# Motherboard.net
KiCad netlist of a schematic drawn in EAGLE
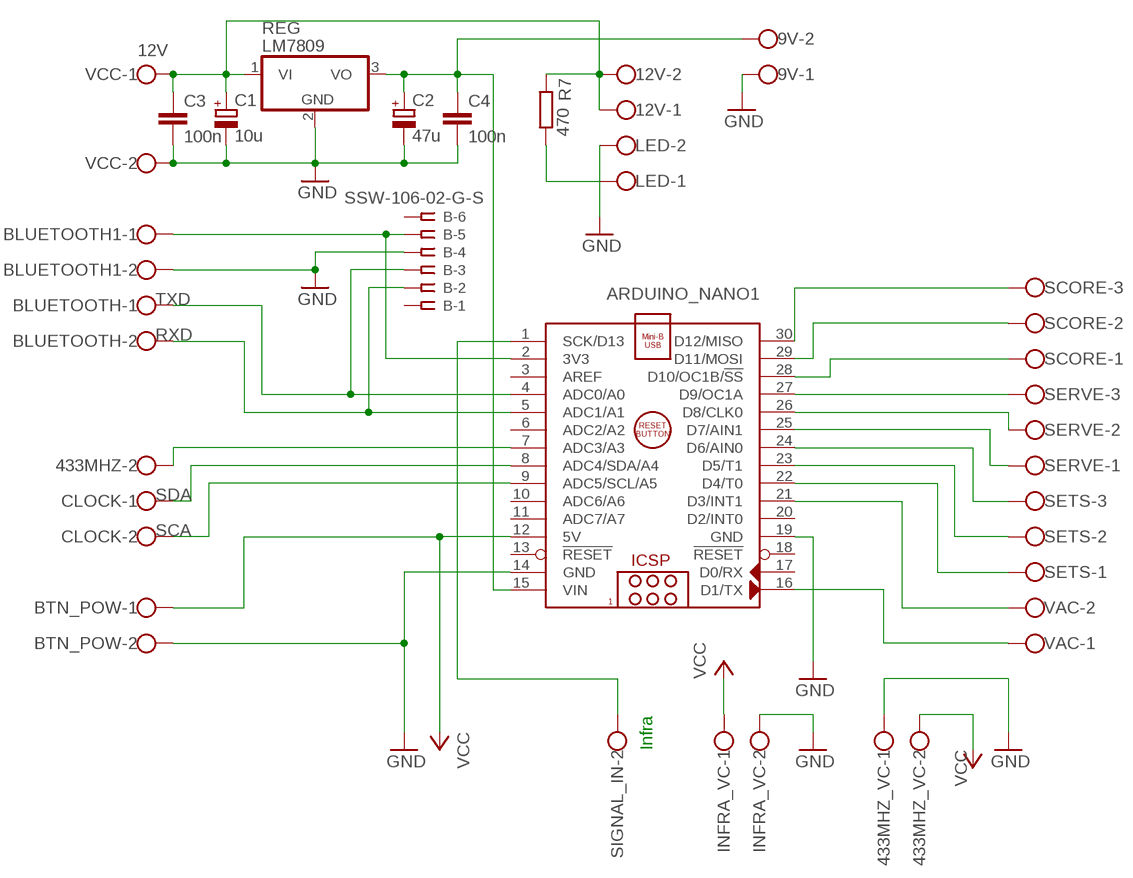
[diagram p0: schematic, sheet 1]

(export (version "E")
  (design (tool "Eeschema 10.0.6"))
  (components
    (comp (ref "9V")
      (value "W237-102")
      (footprint "eagle-import:W237-102")
      (fields (field (name "MPN") "237-102"))
      (libsource (lib "eagle-import") (part "W237-102"))
    )
    (comp (ref "12V")
      (value "W237-102")
      (footprint "eagle-import:W237-102")
      (fields (field (name "MPN") "237-102"))
      (libsource (lib "eagle-import") (part "W237-102"))
    )
    (comp (ref "433MHZ")
      (value "W237-102")
      (footprint "eagle-import:W237-102")
      (fields (field (name "MPN") "237-102"))
      (libsource (lib "eagle-import") (part "W237-102"))
    )
    (comp (ref "433MHZ_VC")
      (value "W237-102")
      (footprint "eagle-import:W237-102")
      (fields (field (name "MPN") "237-102"))
      (libsource (lib "eagle-import") (part "W237-102"))
    )
    (comp (ref "ARDUINO_NANO1")
      (value "ARDUINO_NANO")
      (footprint "eagle-import:ARDUINO_NANO")
      (libsource (lib "eagle-import") (part "ARDUINO_NANO"))
    )
    (comp (ref "B")
      (value "SSW-106-02-G-S")
      (footprint "eagle-import:SSW-106-02-G-S")
      (fields (field (name "MF") "Samtec Inc."))
      (libsource (lib "eagle-import") (part "SSW-106-02-G-S"))
    )
    (comp (ref "BLUETOOTH")
      (value "W237-102")
      (footprint "eagle-import:W237-102")
      (fields (field (name "MPN") "237-102"))
      (libsource (lib "eagle-import") (part "W237-102"))
    )
    (comp (ref "BLUETOOTH1")
      (value "W237-102")
      (footprint "eagle-import:W237-102")
      (fields (field (name "MPN") "237-102"))
      (libsource (lib "eagle-import") (part "W237-102"))
    )
    (comp (ref "BTN_POW")
      (value "W237-102")
      (footprint "eagle-import:W237-102")
      (fields (field (name "MPN") "237-102"))
      (libsource (lib "eagle-import") (part "W237-102"))
    )
    (comp (ref "C1")
      (value "10u")
      (footprint "eagle-import:E2-4")
      (libsource (lib "eagle-import") (part "CPOL-EUE2-4"))
    )
    (comp (ref "C2")
      (value "47u")
      (footprint "eagle-import:E2-4")
      (libsource (lib "eagle-import") (part "CPOL-EUE2-4"))
    )
    (comp (ref "C3")
      (value "100n")
      (footprint "eagle-import:C5B2.5")
      (libsource (lib "eagle-import") (part "C5/2.5"))
    )
    (comp (ref "C4")
      (value "100n")
      (footprint "eagle-import:C5B2.5")
      (libsource (lib "eagle-import") (part "C5/2.5"))
    )
    (comp (ref "CLOCK")
      (value "W237-102")
      (footprint "eagle-import:W237-102")
      (fields (field (name "MPN") "237-102"))
      (libsource (lib "eagle-import") (part "W237-102"))
    )
    (comp (ref "INFRA_VC")
      (value "W237-102")
      (footprint "eagle-import:W237-102")
      (fields (field (name "MPN") "237-102"))
      (libsource (lib "eagle-import") (part "W237-102"))
    )
    (comp (ref "LED")
      (value "W237-102")
      (footprint "eagle-import:W237-102")
      (fields (field (name "MPN") "237-102"))
      (libsource (lib "eagle-import") (part "W237-102"))
    )
    (comp (ref "R7")
      (value "470")
      (footprint "eagle-import:0204_7")
      (libsource (lib "eagle-import") (part "R-EU_0204/7"))
    )
    (comp (ref "REG")
      (value "LM7809")
      (footprint "eagle-import:TO220H")
      (libsource (lib "eagle-import") (part "78T05"))
    )
    (comp (ref "SCORE")
      (value "W237-103")
      (footprint "eagle-import:W237-103")
      (fields (field (name "MPN") "237-103"))
      (libsource (lib "eagle-import") (part "W237-103"))
    )
    (comp (ref "SERVE")
      (value "W237-103")
      (footprint "eagle-import:W237-103")
      (fields (field (name "MPN") "237-103"))
      (libsource (lib "eagle-import") (part "W237-103"))
    )
    (comp (ref "SETS")
      (value "W237-103")
      (footprint "eagle-import:W237-103")
      (fields (field (name "MPN") "237-103"))
      (libsource (lib "eagle-import") (part "W237-103"))
    )
    (comp (ref "SIGNAL_IN")
      (value "W237-102")
      (footprint "eagle-import:W237-102")
      (fields (field (name "MPN") "237-102"))
      (libsource (lib "eagle-import") (part "W237-102"))
    )
    (comp (ref "VAC")
      (value "W237-102")
      (footprint "eagle-import:W237-102")
      (fields (field (name "MPN") "237-102"))
      (libsource (lib "eagle-import") (part "W237-102"))
    )
    (comp (ref "VCC")
      (value "W237-102")
      (footprint "eagle-import:W237-102")
      (fields (field (name "MPN") "237-102"))
      (libsource (lib "eagle-import") (part "W237-102"))
    )
  )
  (nets
    (net (code "1") (name "/12V") (class "Default")
      (node (ref "12V") (pin "1") (pinfunction "KL_1") (pintype "passive"))
      (node (ref "12V") (pin "2") (pinfunction "KL_2") (pintype "passive"))
      (node (ref "C1") (pin "+") (pinfunction "+_+") (pintype "passive"))
      (node (ref "C3") (pin "1") (pinfunction "1_1") (pintype "passive"))
      (node (ref "R7") (pin "2") (pinfunction "2_2") (pintype "passive"))
      (node (ref "REG") (pin "1") (pinfunction "VI_1") (pintype "input"))
      (node (ref "VCC") (pin "1") (pinfunction "KL_1") (pintype "passive"))
    )
    (net (code "2") (name "GND") (class "Default")
      (node (ref "433MHZ_VC") (pin "1") (pinfunction "KL_1") (pintype "passive"))
      (node (ref "9V") (pin "1") (pinfunction "KL_1") (pintype "passive"))
      (node (ref "ARDUINO_NANO1") (pin "14") (pinfunction "GND_14") (pintype "power_in"))
      (node (ref "ARDUINO_NANO1") (pin "19") (pinfunction "GND_19") (pintype "power_in"))
      (node (ref "B") (pin "4") (pinfunction "1_4") (pintype "passive"))
      (node (ref "BLUETOOTH1") (pin "2") (pinfunction "KL_2") (pintype "passive"))
      (node (ref "BTN_POW") (pin "2") (pinfunction "KL_2") (pintype "passive"))
      (node (ref "C1") (pin "-") (pinfunction "-_-") (pintype "passive"))
      (node (ref "C2") (pin "-") (pinfunction "-_-") (pintype "passive"))
      (node (ref "C3") (pin "2") (pinfunction "2_2") (pintype "passive"))
      (node (ref "C4") (pin "2") (pinfunction "2_2") (pintype "passive"))
      (node (ref "INFRA_VC") (pin "2") (pinfunction "KL_2") (pintype "passive"))
      (node (ref "LED") (pin "2") (pinfunction "KL_2") (pintype "passive"))
      (node (ref "REG") (pin "2") (pinfunction "GND_2") (pintype "passive"))
      (node (ref "VCC") (pin "2") (pinfunction "KL_2") (pintype "passive"))
    )
    (net (code "3") (name "Net-(9VB-KL)") (class "Default")
      (node (ref "9V") (pin "2") (pinfunction "KL_2") (pintype "passive"))
      (node (ref "ARDUINO_NANO1") (pin "15") (pinfunction "VIN_15") (pintype "power_in"))
      (node (ref "C2") (pin "+") (pinfunction "+_+") (pintype "passive"))
      (node (ref "C4") (pin "1") (pinfunction "1_1") (pintype "passive"))
      (node (ref "REG") (pin "3") (pinfunction "VO_3") (pintype "passive"))
    )
    (net (code "4") (name "Net-(433MHZB-KL)") (class "Default")
      (node (ref "433MHZ") (pin "2") (pinfunction "KL_2") (pintype "passive"))
      (node (ref "ARDUINO_NANO1") (pin "7") (pinfunction "ADC3/A3_7") (pintype "bidirectional"))
    )
    (net (code "5") (name "Net-(ARDUINO_NANO1-3V3)") (class "Default")
      (node (ref "ARDUINO_NANO1") (pin "2") (pinfunction "3V3_2") (pintype "output"))
      (node (ref "B") (pin "5") (pinfunction "1_5") (pintype "passive"))
      (node (ref "BLUETOOTH1") (pin "1") (pinfunction "KL_1") (pintype "passive"))
    )
    (net (code "6") (name "Net-(ARDUINO_NANO1-ADC0{slash}A0)") (class "Default")
      (node (ref "ARDUINO_NANO1") (pin "4") (pinfunction "ADC0/A0_4") (pintype "bidirectional"))
      (node (ref "B") (pin "3") (pinfunction "1_3") (pintype "passive"))
      (node (ref "BLUETOOTH") (pin "1") (pinfunction "KL_1") (pintype "passive"))
    )
    (net (code "7") (name "Net-(ARDUINO_NANO1-ADC1{slash}A1)") (class "Default")
      (node (ref "ARDUINO_NANO1") (pin "5") (pinfunction "ADC1/A1_5") (pintype "bidirectional"))
      (node (ref "B") (pin "2") (pinfunction "1_2") (pintype "passive"))
      (node (ref "BLUETOOTH") (pin "2") (pinfunction "KL_2") (pintype "passive"))
    )
    (net (code "8") (name "Net-(ARDUINO_NANO1-ADC4{slash}SDA{slash}A4)") (class "Default")
      (node (ref "ARDUINO_NANO1") (pin "8") (pinfunction "ADC4/SDA/A4_8") (pintype "bidirectional"))
      (node (ref "CLOCK") (pin "1") (pinfunction "KL_1") (pintype "passive"))
    )
    (net (code "9") (name "Net-(ARDUINO_NANO1-ADC5{slash}SCL{slash}A5)") (class "Default")
      (node (ref "ARDUINO_NANO1") (pin "9") (pinfunction "ADC5/SCL/A5_9") (pintype "bidirectional"))
      (node (ref "CLOCK") (pin "2") (pinfunction "KL_2") (pintype "passive"))
    )
    (net (code "10") (name "Net-(ARDUINO_NANO1-D1{slash}TX)") (class "Default")
      (node (ref "ARDUINO_NANO1") (pin "16") (pinfunction "D1/TX_16") (pintype "bidirectional"))
      (node (ref "VAC") (pin "1") (pinfunction "KL_1") (pintype "passive"))
    )
    (net (code "11") (name "Net-(ARDUINO_NANO1-D3{slash}INT1)") (class "Default")
      (node (ref "ARDUINO_NANO1") (pin "21") (pinfunction "D3/INT1_21") (pintype "bidirectional"))
      (node (ref "VAC") (pin "2") (pinfunction "KL_2") (pintype "passive"))
    )
    (net (code "12") (name "Net-(ARDUINO_NANO1-D4{slash}T0)") (class "Default")
      (node (ref "ARDUINO_NANO1") (pin "22") (pinfunction "D4/T0_22") (pintype "bidirectional"))
      (node (ref "SETS") (pin "1") (pinfunction "KL_1") (pintype "passive"))
    )
    (net (code "13") (name "Net-(ARDUINO_NANO1-D5{slash}T1)") (class "Default")
      (node (ref "ARDUINO_NANO1") (pin "23") (pinfunction "D5/T1_23") (pintype "bidirectional"))
      (node (ref "SETS") (pin "2") (pinfunction "KL_2") (pintype "passive"))
    )
    (net (code "14") (name "Net-(ARDUINO_NANO1-D6{slash}AIN0)") (class "Default")
      (node (ref "ARDUINO_NANO1") (pin "24") (pinfunction "D6/AIN0_24") (pintype "bidirectional"))
      (node (ref "SETS") (pin "3") (pinfunction "KL_3") (pintype "passive"))
    )
    (net (code "15") (name "Net-(ARDUINO_NANO1-D7{slash}AIN1)") (class "Default")
      (node (ref "ARDUINO_NANO1") (pin "25") (pinfunction "D7/AIN1_25") (pintype "bidirectional"))
      (node (ref "SERVE") (pin "1") (pinfunction "KL_1") (pintype "passive"))
    )
    (net (code "16") (name "Net-(ARDUINO_NANO1-D8{slash}CLK0)") (class "Default")
      (node (ref "ARDUINO_NANO1") (pin "26") (pinfunction "D8/CLK0_26") (pintype "bidirectional"))
      (node (ref "SERVE") (pin "2") (pinfunction "KL_2") (pintype "passive"))
    )
    (net (code "17") (name "Net-(ARDUINO_NANO1-D9{slash}OC1A)") (class "Default")
      (node (ref "ARDUINO_NANO1") (pin "27") (pinfunction "D9/OC1A_27") (pintype "bidirectional"))
      (node (ref "SERVE") (pin "3") (pinfunction "KL_3") (pintype "passive"))
    )
    (net (code "18") (name "Net-(ARDUINO_NANO1-D10{slash}OC1B{slash}~{SS})") (class "Default")
      (node (ref "ARDUINO_NANO1") (pin "28") (pinfunction "D10/OC1B/~{SS}_28") (pintype "bidirectional"))
      (node (ref "SCORE") (pin "1") (pinfunction "KL_1") (pintype "passive"))
    )
    (net (code "19") (name "Net-(ARDUINO_NANO1-D11{slash}MOSI)") (class "Default")
      (node (ref "ARDUINO_NANO1") (pin "29") (pinfunction "D11/MOSI_29") (pintype "bidirectional"))
      (node (ref "SCORE") (pin "2") (pinfunction "KL_2") (pintype "passive"))
    )
    (net (code "20") (name "Net-(ARDUINO_NANO1-D12{slash}MISO)") (class "Default")
      (node (ref "ARDUINO_NANO1") (pin "30") (pinfunction "D12/MISO_30") (pintype "bidirectional"))
      (node (ref "SCORE") (pin "3") (pinfunction "KL_3") (pintype "passive"))
    )
    (net (code "21") (name "Net-(ARDUINO_NANO1-SCK{slash}D13)") (class "Default")
      (node (ref "ARDUINO_NANO1") (pin "1") (pinfunction "SCK/D13_1") (pintype "bidirectional"))
      (node (ref "SIGNAL_IN") (pin "2") (pinfunction "KL_2") (pintype "passive"))
    )
    (net (code "22") (name "Net-(LEDA-KL)") (class "Default")
      (node (ref "LED") (pin "1") (pinfunction "KL_1") (pintype "passive"))
      (node (ref "R7") (pin "1") (pinfunction "1_1") (pintype "passive"))
    )
    (net (code "23") (name "VCC") (class "Default")
      (node (ref "433MHZ_VC") (pin "2") (pinfunction "KL_2") (pintype "passive"))
      (node (ref "ARDUINO_NANO1") (pin "12") (pinfunction "5V_12") (pintype "power_in"))
      (node (ref "BTN_POW") (pin "1") (pinfunction "KL_1") (pintype "passive"))
      (node (ref "INFRA_VC") (pin "1") (pinfunction "KL_1") (pintype "passive"))
    )
    (net (code "24") (name "unconnected-(ARDUINO_NANO1-ADC2{slash}A2-Pad6)") (class "Default")
      (node (ref "ARDUINO_NANO1") (pin "6") (pinfunction "ADC2/A2_6") (pintype "bidirectional"))
    )
    (net (code "25") (name "unconnected-(ARDUINO_NANO1-ADC6{slash}A6-Pad10)") (class "Default")
      (node (ref "ARDUINO_NANO1") (pin "10") (pinfunction "ADC6/A6_10") (pintype "bidirectional"))
    )
    (net (code "26") (name "unconnected-(ARDUINO_NANO1-ADC7{slash}A7-Pad11)") (class "Default")
      (node (ref "ARDUINO_NANO1") (pin "11") (pinfunction "ADC7/A7_11") (pintype "bidirectional"))
    )
    (net (code "27") (name "unconnected-(ARDUINO_NANO1-AREF-Pad3)") (class "Default")
      (node (ref "ARDUINO_NANO1") (pin "3") (pinfunction "AREF_3") (pintype "input"))
    )
    (net (code "28") (name "unconnected-(ARDUINO_NANO1-D0{slash}RX-Pad17)") (class "Default")
      (node (ref "ARDUINO_NANO1") (pin "17") (pinfunction "D0/RX_17") (pintype "bidirectional"))
    )
    (net (code "29") (name "unconnected-(ARDUINO_NANO1-D2{slash}INT0-Pad20)") (class "Default")
      (node (ref "ARDUINO_NANO1") (pin "20") (pinfunction "D2/INT0_20") (pintype "bidirectional"))
    )
    (net (code "30") (name "unconnected-(ARDUINO_NANO1-~{RESET}-Pad13)") (class "Default")
      (node (ref "ARDUINO_NANO1") (pin "13") (pinfunction "~{RESET}_13") (pintype "input"))
    )
    (net (code "31") (name "unconnected-(ARDUINO_NANO1-~{RESET}-Pad18)") (class "Default")
      (node (ref "ARDUINO_NANO1") (pin "18") (pinfunction "~{RESET}_18") (pintype "input"))
    )
    (net (code "32") (name "unconnected-(B-Pad1)") (class "Default")
      (node (ref "B") (pin "1") (pinfunction "1_1") (pintype "passive"))
    )
    (net (code "33") (name "unconnected-(BF-1-Pad6)") (class "Default")
      (node (ref "B") (pin "6") (pinfunction "1_6") (pintype "passive"))
    )
  )
)
